# BoutVoeding.net
KiCad netlist of a schematic drawn in Altium Designer
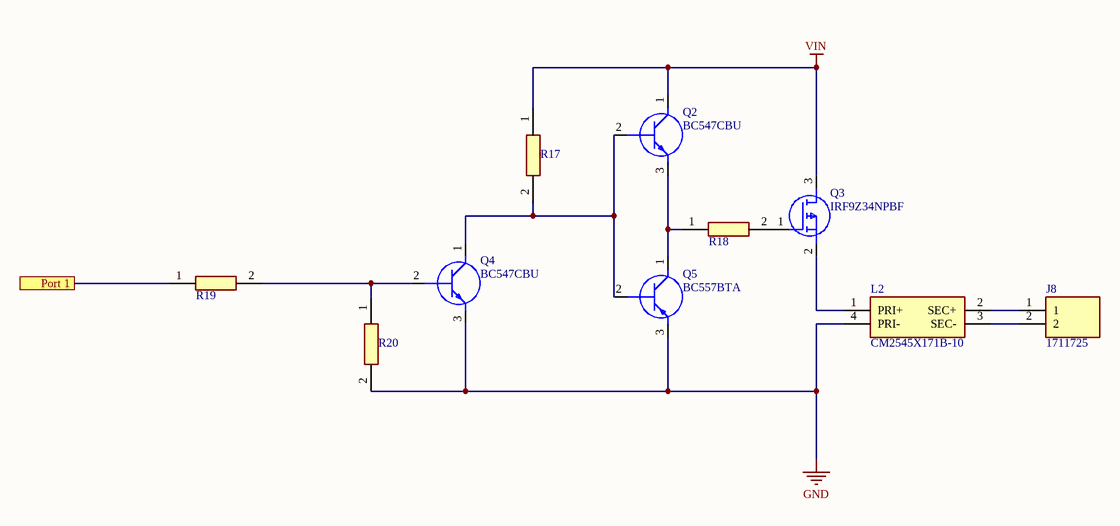
[diagram p0: BoutVoeding.SchDoc]

(export (version "E")
  (design (tool "Eeschema 10.0.6"))
  (components
    (comp (ref "J8")
      (value "1711725")
      (footprint "1711725")
      (description "Connector")
      (libsource (lib "Schlib1") (part "1711725"))
    )
    (comp (ref "L2")
      (value "CM2545X171B-10")
      (footprint "CM2545X171B10")
      (description "Transformer")
      (libsource (lib "Schlib1") (part "CM2545X171B-10"))
    )
    (comp (ref "Q2")
      (value "BC547CBU")
      (footprint "TTTT")
      (description "Transistor BJT NPN")
      (libsource (lib "Schlib1") (part "BC547CBU"))
    )
    (comp (ref "Q3")
      (value "IRF9Z34NPBF")
      (footprint "T2")
      (description "MOSFET (P-Channel)")
      (fields (field (name "MOUSER2 PART NUMBER") "942-IRF9Z34NPBF"))
      (libsource (lib "Schlib1") (part "IRF9Z34NPBF"))
    )
    (comp (ref "Q4")
      (value "BC547CBU")
      (footprint "TTTT")
      (description "Transistor BJT NPN")
      (libsource (lib "Schlib1") (part "BC547CBU"))
    )
    (comp (ref "Q5")
      (value "BC557BTA")
      (footprint "TTTT")
      (description "Transistor BJT PNP")
      (fields (field (name "MOUSER2 PART NUMBER") "512-BC557BTA"))
      (libsource (lib "Schlib1") (part "BC557BTA"))
    )
    (comp (ref "R17")
      (value "CRCW08054K70FKEAHP")
      (footprint "Resistor")
      (description "Resistor 4.7KOhm")
      (fields (field (name "MOUSER2 PART NUMBER") "71-CRCW08054K70FKEAH"))
      (libsource (lib "Schlib1") (part "CRCW08054K70FKEAHP"))
    )
    (comp (ref "R18")
      (value "CPF0805B18KE")
      (footprint "Resistor")
      (description "Resistor 100Ohm")
      (libsource (lib "Schlib1") (part "CPF0805B18KE"))
    )
    (comp (ref "R19")
      (value "CRCW080510K0DHEAP")
      (footprint "Resistor")
      (description "Resistor 10KOhm")
      (libsource (lib "Schlib1") (part "CRCW080510K0DHEAP"))
    )
    (comp (ref "R20")
      (value "CRCW08054K70FKEAHP")
      (footprint "Resistor")
      (description "Resistor 4.7KOhm")
      (fields (field (name "MOUSER2 PART NUMBER") "71-CRCW08054K70FKEAH"))
      (libsource (lib "Schlib1") (part "CRCW08054K70FKEAHP"))
    )
  )
  (nets
    (net (code "1") (name "/Port 1") (class "Default")
      (node (ref "R19") (pin "1") (pinfunction "1_1") (pintype "passive"))
    )
    (net (code "2") (name "GND") (class "Default")
      (node (ref "L2") (pin "4") (pinfunction "PRI-_4") (pintype "passive"))
      (node (ref "Q4") (pin "3") (pinfunction "E_3") (pintype "passive"))
      (node (ref "Q5") (pin "3") (pinfunction "E_3") (pintype "passive"))
      (node (ref "R20") (pin "2") (pinfunction "2_2") (pintype "passive"))
    )
    (net (code "3") (name "Net-(L2-PRI+)") (class "Default")
      (node (ref "L2") (pin "1") (pinfunction "PRI+_1") (pintype "passive"))
      (node (ref "Q3") (pin "2") (pinfunction "S_2") (pintype "passive"))
    )
    (net (code "4") (name "Net-(L2-SEC+)") (class "Default")
      (node (ref "J8") (pin "1") (pinfunction "1_1") (pintype "passive"))
      (node (ref "L2") (pin "2") (pinfunction "SEC+_2") (pintype "passive"))
    )
    (net (code "5") (name "Net-(L2-SEC-)") (class "Default")
      (node (ref "J8") (pin "2") (pinfunction "2_2") (pintype "passive"))
      (node (ref "L2") (pin "3") (pinfunction "SEC-_3") (pintype "passive"))
    )
    (net (code "6") (name "Net-(Q2-B)") (class "Default")
      (node (ref "Q2") (pin "2") (pinfunction "B_2") (pintype "passive"))
      (node (ref "Q4") (pin "1") (pinfunction "C_1") (pintype "passive"))
      (node (ref "Q5") (pin "2") (pinfunction "B_2") (pintype "passive"))
      (node (ref "R17") (pin "2") (pinfunction "2_2") (pintype "passive"))
    )
    (net (code "7") (name "Net-(Q2-E)") (class "Default")
      (node (ref "Q2") (pin "3") (pinfunction "E_3") (pintype "passive"))
      (node (ref "Q5") (pin "1") (pinfunction "C_1") (pintype "passive"))
      (node (ref "R18") (pin "1") (pinfunction "1_1") (pintype "passive"))
    )
    (net (code "8") (name "Net-(Q3-G)") (class "Default")
      (node (ref "Q3") (pin "1") (pinfunction "G_1") (pintype "passive"))
      (node (ref "R18") (pin "2") (pinfunction "2_2") (pintype "passive"))
    )
    (net (code "9") (name "Net-(Q4-B)") (class "Default")
      (node (ref "Q4") (pin "2") (pinfunction "B_2") (pintype "passive"))
      (node (ref "R19") (pin "2") (pinfunction "2_2") (pintype "passive"))
      (node (ref "R20") (pin "1") (pinfunction "1_1") (pintype "passive"))
    )
    (net (code "10") (name "VIN") (class "Default")
      (node (ref "Q2") (pin "1") (pinfunction "C_1") (pintype "passive"))
      (node (ref "Q3") (pin "3") (pinfunction "D_3") (pintype "passive"))
      (node (ref "R17") (pin "1") (pinfunction "1_1") (pintype "passive"))
    )
  )
)
